# PowerModule_Testboard.net
KiCad netlist of a schematic drawn in EAGLE
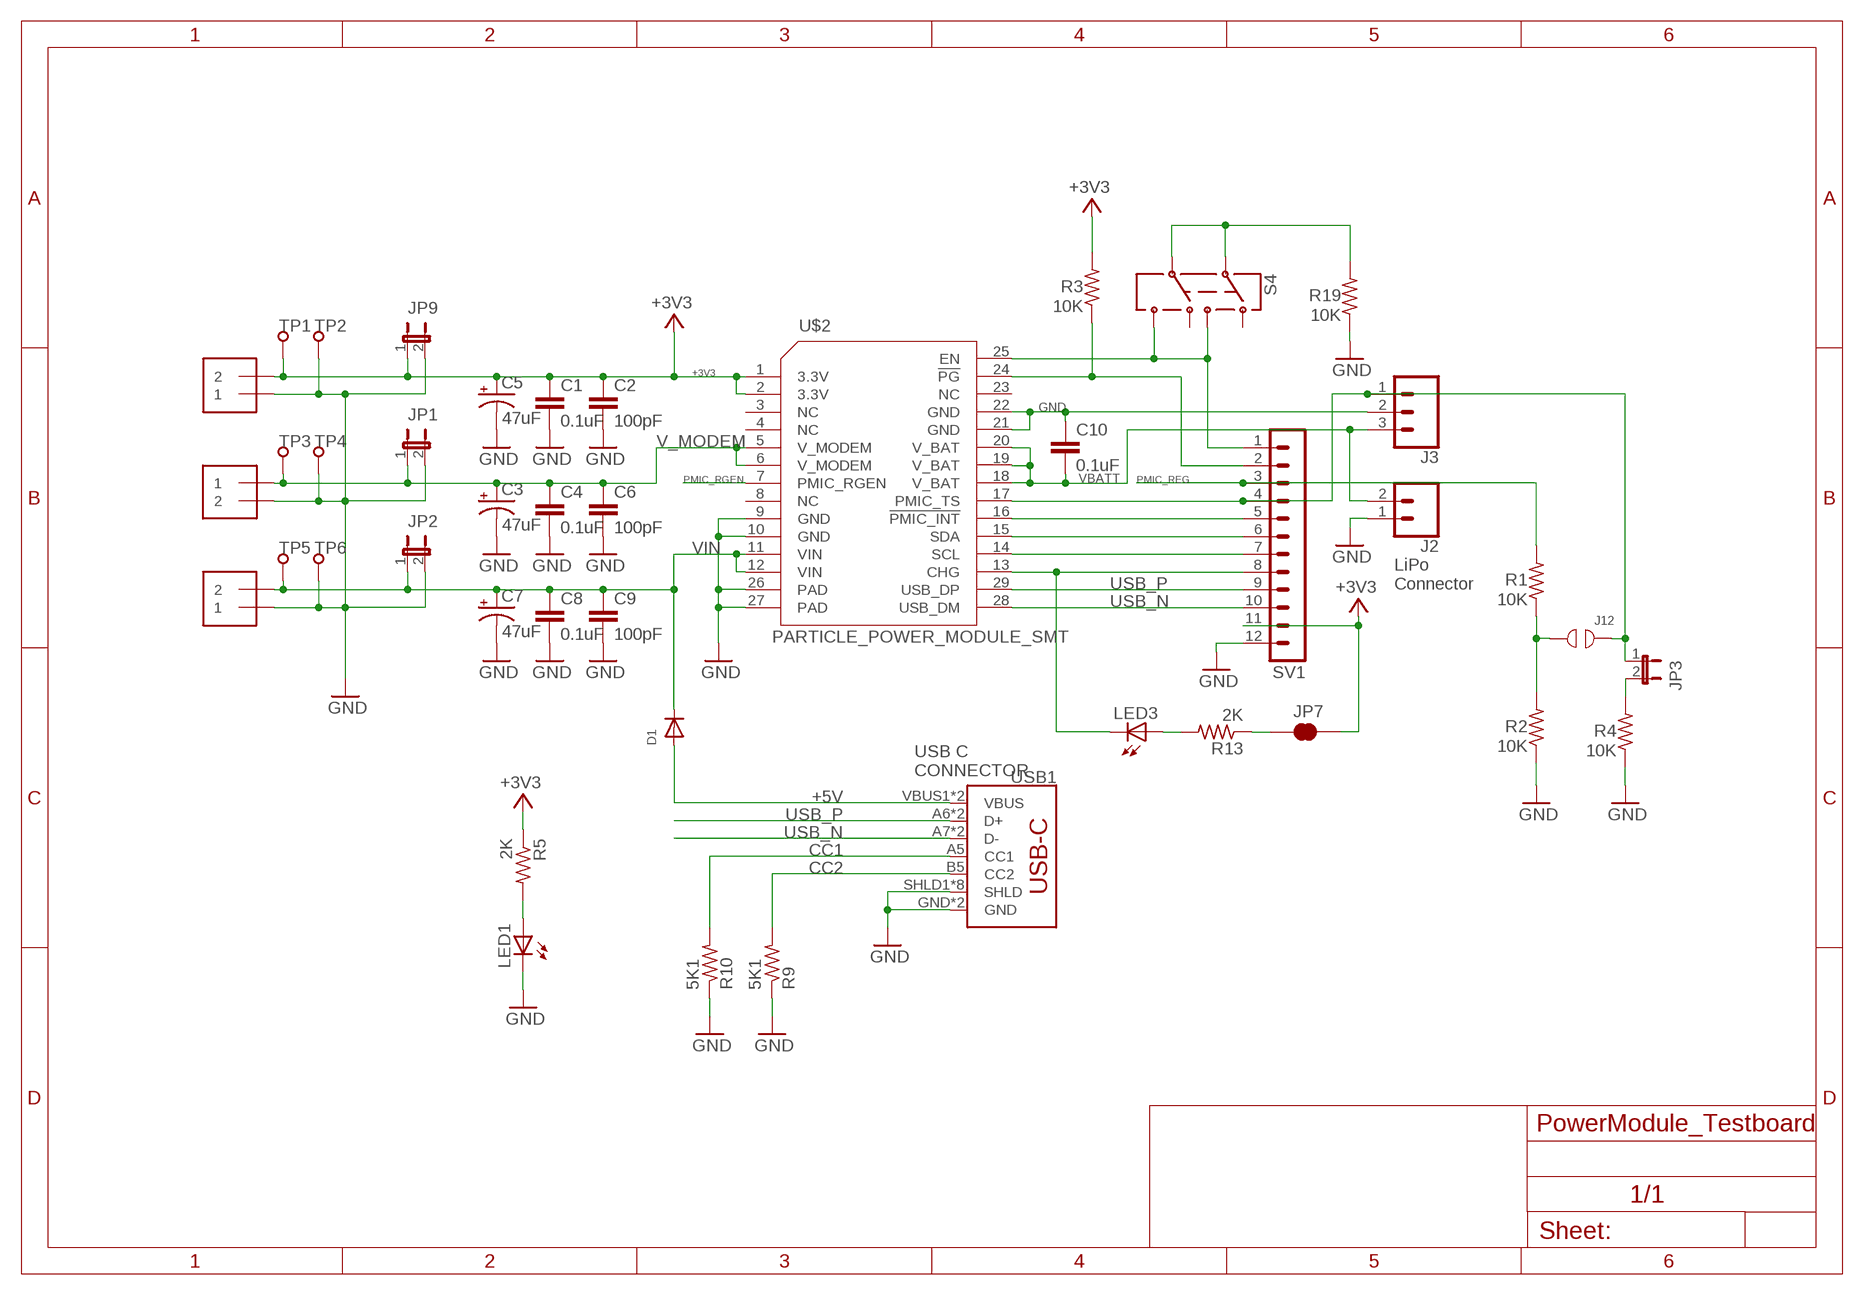
[diagram p0: schematic, sheet 1]

(export (version "E")
  (design (tool "Eeschema 10.0.6"))
  (components
    (comp (ref "C1")
      (value "0.1uF")
      (footprint "eagle-import:0603")
      (libsource (lib "eagle-import") (part "0.1UF-0603-25V-5%"))
    )
    (comp (ref "C2")
      (value "100pF")
      (footprint "eagle-import:0603")
      (libsource (lib "eagle-import") (part "0.1UF-0603-25V-5%"))
    )
    (comp (ref "C3")
      (value "47uF")
      (footprint "eagle-import:NIC_10X10.5_CAP")
      (libsource (lib "eagle-import") (part "100UF-POLAR-10X10.5-63V-20%"))
    )
    (comp (ref "C4")
      (value "0.1uF")
      (footprint "eagle-import:0603")
      (libsource (lib "eagle-import") (part "0.1UF-0603-25V-5%"))
    )
    (comp (ref "C5")
      (value "47uF")
      (footprint "eagle-import:NIC_10X10.5_CAP")
      (libsource (lib "eagle-import") (part "100UF-POLAR-10X10.5-63V-20%"))
    )
    (comp (ref "C6")
      (value "100pF")
      (footprint "eagle-import:0603")
      (libsource (lib "eagle-import") (part "0.1UF-0603-25V-5%"))
    )
    (comp (ref "C7")
      (value "47uF")
      (footprint "eagle-import:NIC_10X10.5_CAP")
      (libsource (lib "eagle-import") (part "100UF-POLAR-10X10.5-63V-20%"))
    )
    (comp (ref "C8")
      (value "0.1uF")
      (footprint "eagle-import:0603")
      (libsource (lib "eagle-import") (part "0.1UF-0603-25V-5%"))
    )
    (comp (ref "C9")
      (value "100pF")
      (footprint "eagle-import:0603")
      (libsource (lib "eagle-import") (part "0.1UF-0603-25V-5%"))
    )
    (comp (ref "C10")
      (value "0.1uF")
      (footprint "eagle-import:0603")
      (libsource (lib "eagle-import") (part "0.1UF-0603-25V-5%"))
    )
    (comp (ref "D1")
      (value "DIODE_SOD-123FL")
      (footprint "eagle-import:SOD-123FL")
      (libsource (lib "eagle-import") (part "DIODE_SOD-123FL"))
    )
    (comp (ref "J1")
      (value "1X2-3.5MM")
      (footprint "eagle-import:1X2-3.5MM")
      (libsource (lib "eagle-import") (part "1X2-3.5MM"))
    )
    (comp (ref "J2")
      (value "CONN_02-JST-2MM-SMT")
      (footprint "eagle-import:JST-2-SMD@2")
      (libsource (lib "eagle-import") (part "CONN_02-JST-2MM-SMT"))
    )
    (comp (ref "J3")
      (value "CONN_03JST-SMD-VERT")
      (footprint "eagle-import:JST-3-SMD-VERT")
      (libsource (lib "eagle-import") (part "CONN_03JST-SMD-VERT"))
    )
    (comp (ref "J4")
      (value "1X2-3.5MM")
      (footprint "eagle-import:1X2-3.5MM")
      (libsource (lib "eagle-import") (part "1X2-3.5MM"))
    )
    (comp (ref "J5")
      (value "1X2-3.5MM")
      (footprint "eagle-import:1X2-3.5MM")
      (libsource (lib "eagle-import") (part "1X2-3.5MM"))
    )
    (comp (ref "J12")
      (value "TP_OPEN")
      (footprint "eagle-import:TP_OPEN")
      (libsource (lib "eagle-import") (part "TP_OPEN"))
    )
    (comp (ref "JP1")
      (value "JUMPER2")
      (footprint "eagle-import:JUMPER2")
      (libsource (lib "eagle-import") (part "JUMPER2"))
    )
    (comp (ref "JP2")
      (value "JUMPER2")
      (footprint "eagle-import:JUMPER2")
      (libsource (lib "eagle-import") (part "JUMPER2"))
    )
    (comp (ref "JP3")
      (value "JUMPER2")
      (footprint "eagle-import:JUMPER2")
      (libsource (lib "eagle-import") (part "JUMPER2"))
    )
    (comp (ref "JP7")
      (value "JUMPER-SMT_2_NC_TRACE_NO-SILK")
      (footprint "eagle-import:SMT-JUMPER_2_NC_TRACE_NO-SILK")
      (libsource (lib "eagle-import") (part "JUMPER-SMT_2_NC_TRACE_NO-SILK"))
    )
    (comp (ref "JP9")
      (value "JUMPER2")
      (footprint "eagle-import:JUMPER2")
      (libsource (lib "eagle-import") (part "JUMPER2"))
    )
    (comp (ref "LED1")
      (value "LEDCHIP-LED0603")
      (footprint "eagle-import:CHIP-LED0603")
      (libsource (lib "eagle-import") (part "LEDCHIP-LED0603"))
    )
    (comp (ref "LED3")
      (value "LEDCHIP-LED0603")
      (footprint "eagle-import:CHIP-LED0603")
      (libsource (lib "eagle-import") (part "LEDCHIP-LED0603"))
    )
    (comp (ref "R1")
      (value "10K")
      (footprint "eagle-import:R0603_P")
      (libsource (lib "eagle-import") (part "RES_0603100K_"))
    )
    (comp (ref "R2")
      (value "10K")
      (footprint "eagle-import:R0603_P")
      (libsource (lib "eagle-import") (part "RES_0603100K_"))
    )
    (comp (ref "R3")
      (value "10K")
      (footprint "eagle-import:R0603_P")
      (libsource (lib "eagle-import") (part "RES_0603100K_"))
    )
    (comp (ref "R4")
      (value "10K")
      (footprint "eagle-import:R0603_P")
      (libsource (lib "eagle-import") (part "RES_0603100K_"))
    )
    (comp (ref "R5")
      (value "2K")
      (footprint "eagle-import:R0603_P")
      (libsource (lib "eagle-import") (part "RES_06032K2_"))
    )
    (comp (ref "R9")
      (value "5K1")
      (footprint "eagle-import:R0603_P")
      (libsource (lib "eagle-import") (part "RES_0603"))
    )
    (comp (ref "R10")
      (value "5K1")
      (footprint "eagle-import:R0603_P")
      (libsource (lib "eagle-import") (part "RES_0603"))
    )
    (comp (ref "R13")
      (value "2K")
      (footprint "eagle-import:R0603_P")
      (libsource (lib "eagle-import") (part "RES_06032K2_"))
    )
    (comp (ref "R19")
      (value "10K")
      (footprint "eagle-import:R0603_P")
      (libsource (lib "eagle-import") (part "RES_0603100K_"))
    )
    (comp (ref "S4")
      (value "SWITCH-DPDT")
      (footprint "eagle-import:SWITCH-2.5X3.2-6")
      (libsource (lib "eagle-import") (part "SWITCH-DPDT"))
    )
    (comp (ref "SV1")
      (value "MA12-1")
      (footprint "eagle-import:MA12-1")
      (libsource (lib "eagle-import") (part "MA12-1"))
    )
    (comp (ref "TP1")
      (value "TP-S2751-46R")
      (footprint "eagle-import:S2751-46R")
      (libsource (lib "eagle-import") (part "TP-S2751-46R"))
    )
    (comp (ref "TP2")
      (value "TP-S2751-46R")
      (footprint "eagle-import:S2751-46R")
      (libsource (lib "eagle-import") (part "TP-S2751-46R"))
    )
    (comp (ref "TP3")
      (value "TP-S2751-46R")
      (footprint "eagle-import:S2751-46R")
      (libsource (lib "eagle-import") (part "TP-S2751-46R"))
    )
    (comp (ref "TP4")
      (value "TP-S2751-46R")
      (footprint "eagle-import:S2751-46R")
      (libsource (lib "eagle-import") (part "TP-S2751-46R"))
    )
    (comp (ref "TP5")
      (value "TP-S2751-46R")
      (footprint "eagle-import:S2751-46R")
      (libsource (lib "eagle-import") (part "TP-S2751-46R"))
    )
    (comp (ref "TP6")
      (value "TP-S2751-46R")
      (footprint "eagle-import:S2751-46R")
      (libsource (lib "eagle-import") (part "TP-S2751-46R"))
    )
    (comp (ref "U$2")
      (value "PARTICLE_POWER_MODULE_SMT")
      (footprint "eagle-import:PARTICLE_POWER_MODULE_SMT")
      (libsource (lib "eagle-import") (part "PARTICLE_POWER_MODULE_SMT"))
    )
    (comp (ref "USB1")
      (value "USB_C16PIN")
      (footprint "eagle-import:USB-C-16P")
      (libsource (lib "eagle-import") (part "USB_C16PIN"))
    )
  )
  (nets
    (net (code "1") (name "+3V3") (class "Default")
      (node (ref "C1") (pin "1") (pinfunction "1_1") (pintype "passive"))
      (node (ref "C2") (pin "1") (pinfunction "1_1") (pintype "passive"))
      (node (ref "C5") (pin "+") (pinfunction "+_+") (pintype "passive"))
      (node (ref "J4") (pin "2") (pinfunction "2_2") (pintype "passive"))
      (node (ref "JP7") (pin "1") (pinfunction "1_1") (pintype "passive"))
      (node (ref "JP9") (pin "1") (pinfunction "1_1") (pintype "passive"))
      (node (ref "R3") (pin "2") (pinfunction "2_2") (pintype "passive"))
      (node (ref "R5") (pin "1") (pinfunction "1_1") (pintype "passive"))
      (node (ref "SV1") (pin "11") (pinfunction "11_11") (pintype "passive"))
      (node (ref "TP1") (pin "1") (pinfunction "TP_1") (pintype "bidirectional"))
      (node (ref "U$2") (pin "1") (pinfunction "3.3V_1") (pintype "bidirectional"))
      (node (ref "U$2") (pin "2") (pinfunction "3.3V_2") (pintype "bidirectional"))
    )
    (net (code "2") (name "/+5V") (class "Default")
      (node (ref "D1") (pin "A") (pinfunction "A_A") (pintype "passive"))
      (node (ref "USB1") (pin "VBUS1") (pinfunction "VBUS_VBUS1") (pintype "bidirectional"))
      (node (ref "USB1") (pin "VBUS2") (pinfunction "VBUS_VBUS2") (pintype "bidirectional"))
    )
    (net (code "3") (name "/CC1") (class "Default")
      (node (ref "R10") (pin "2") (pinfunction "2_2") (pintype "passive"))
      (node (ref "USB1") (pin "A5") (pinfunction "CC1_A5") (pintype "bidirectional"))
    )
    (net (code "4") (name "/CC2") (class "Default")
      (node (ref "R9") (pin "2") (pinfunction "2_2") (pintype "passive"))
      (node (ref "USB1") (pin "B5") (pinfunction "CC2_B5") (pintype "bidirectional"))
    )
    (net (code "5") (name "/PMIC_REG") (class "Default")
      (node (ref "R1") (pin "2") (pinfunction "2_2") (pintype "passive"))
      (node (ref "SV1") (pin "3") (pinfunction "3_3") (pintype "passive"))
    )
    (net (code "6") (name "/PMIC_RGEN") (class "Default")
      (node (ref "U$2") (pin "7") (pinfunction "PMIC_RGEN_7") (pintype "bidirectional"))
    )
    (net (code "7") (name "/USB_N") (class "Default")
      (node (ref "SV1") (pin "10") (pinfunction "10_10") (pintype "passive"))
      (node (ref "U$2") (pin "28") (pinfunction "USB_DM_28") (pintype "bidirectional"))
      (node (ref "USB1") (pin "A7") (pinfunction "D-_A7") (pintype "bidirectional"))
      (node (ref "USB1") (pin "B7") (pinfunction "D-_B7") (pintype "bidirectional"))
    )
    (net (code "8") (name "/USB_P") (class "Default")
      (node (ref "SV1") (pin "9") (pinfunction "9_9") (pintype "passive"))
      (node (ref "U$2") (pin "29") (pinfunction "USB_DP_29") (pintype "bidirectional"))
      (node (ref "USB1") (pin "A6") (pinfunction "D+_A6") (pintype "bidirectional"))
      (node (ref "USB1") (pin "B6") (pinfunction "D+_B6") (pintype "bidirectional"))
    )
    (net (code "9") (name "/VBATT") (class "Default")
      (node (ref "C10") (pin "2") (pinfunction "2_2") (pintype "passive"))
      (node (ref "J2") (pin "2") (pinfunction "1_2") (pintype "passive"))
      (node (ref "J3") (pin "3") (pinfunction "3_3") (pintype "passive"))
      (node (ref "U$2") (pin "18") (pinfunction "V_BAT_18") (pintype "bidirectional"))
      (node (ref "U$2") (pin "19") (pinfunction "V_BAT_19") (pintype "bidirectional"))
      (node (ref "U$2") (pin "20") (pinfunction "V_BAT_20") (pintype "bidirectional"))
    )
    (net (code "10") (name "/VIN") (class "Default")
      (node (ref "C7") (pin "+") (pinfunction "+_+") (pintype "passive"))
      (node (ref "C8") (pin "1") (pinfunction "1_1") (pintype "passive"))
      (node (ref "C9") (pin "1") (pinfunction "1_1") (pintype "passive"))
      (node (ref "D1") (pin "C") (pinfunction "C_C") (pintype "passive"))
      (node (ref "J5") (pin "2") (pinfunction "2_2") (pintype "passive"))
      (node (ref "JP2") (pin "1") (pinfunction "1_1") (pintype "passive"))
      (node (ref "TP5") (pin "1") (pinfunction "TP_1") (pintype "bidirectional"))
      (node (ref "U$2") (pin "11") (pinfunction "VIN_11") (pintype "bidirectional"))
      (node (ref "U$2") (pin "12") (pinfunction "VIN_12") (pintype "bidirectional"))
    )
    (net (code "11") (name "/V_MODEM") (class "Default")
      (node (ref "C3") (pin "+") (pinfunction "+_+") (pintype "passive"))
      (node (ref "C4") (pin "1") (pinfunction "1_1") (pintype "passive"))
      (node (ref "C6") (pin "1") (pinfunction "1_1") (pintype "passive"))
      (node (ref "J1") (pin "1") (pinfunction "1_1") (pintype "passive"))
      (node (ref "JP1") (pin "1") (pinfunction "1_1") (pintype "passive"))
      (node (ref "TP3") (pin "1") (pinfunction "TP_1") (pintype "bidirectional"))
      (node (ref "U$2") (pin "5") (pinfunction "V_MODEM_5") (pintype "bidirectional"))
      (node (ref "U$2") (pin "6") (pinfunction "V_MODEM_6") (pintype "bidirectional"))
    )
    (net (code "12") (name "GND") (class "Default")
      (node (ref "C1") (pin "2") (pinfunction "2_2") (pintype "passive"))
      (node (ref "C10") (pin "1") (pinfunction "1_1") (pintype "passive"))
      (node (ref "C2") (pin "2") (pinfunction "2_2") (pintype "passive"))
      (node (ref "C3") (pin "-") (pinfunction "-_-") (pintype "passive"))
      (node (ref "C4") (pin "2") (pinfunction "2_2") (pintype "passive"))
      (node (ref "C5") (pin "-") (pinfunction "-_-") (pintype "passive"))
      (node (ref "C6") (pin "2") (pinfunction "2_2") (pintype "passive"))
      (node (ref "C7") (pin "-") (pinfunction "-_-") (pintype "passive"))
      (node (ref "C8") (pin "2") (pinfunction "2_2") (pintype "passive"))
      (node (ref "C9") (pin "2") (pinfunction "2_2") (pintype "passive"))
      (node (ref "J1") (pin "2") (pinfunction "2_2") (pintype "passive"))
      (node (ref "J2") (pin "1") (pinfunction "2_1") (pintype "passive"))
      (node (ref "J3") (pin "2") (pinfunction "2_2") (pintype "passive"))
      (node (ref "J4") (pin "1") (pinfunction "1_1") (pintype "passive"))
      (node (ref "J5") (pin "1") (pinfunction "1_1") (pintype "passive"))
      (node (ref "JP1") (pin "2") (pinfunction "2_2") (pintype "passive"))
      (node (ref "JP2") (pin "2") (pinfunction "2_2") (pintype "passive"))
      (node (ref "JP9") (pin "2") (pinfunction "2_2") (pintype "passive"))
      (node (ref "LED1") (pin "C") (pinfunction "C_C") (pintype "passive"))
      (node (ref "R10") (pin "1") (pinfunction "1_1") (pintype "passive"))
      (node (ref "R19") (pin "1") (pinfunction "1_1") (pintype "passive"))
      (node (ref "R2") (pin "1") (pinfunction "1_1") (pintype "passive"))
      (node (ref "R4") (pin "1") (pinfunction "1_1") (pintype "passive"))
      (node (ref "R9") (pin "1") (pinfunction "1_1") (pintype "passive"))
      (node (ref "SV1") (pin "12") (pinfunction "12_12") (pintype "passive"))
      (node (ref "TP2") (pin "1") (pinfunction "TP_1") (pintype "bidirectional"))
      (node (ref "TP4") (pin "1") (pinfunction "TP_1") (pintype "bidirectional"))
      (node (ref "TP6") (pin "1") (pinfunction "TP_1") (pintype "bidirectional"))
      (node (ref "U$2") (pin "10") (pinfunction "GND_10") (pintype "bidirectional"))
      (node (ref "U$2") (pin "21") (pinfunction "GND_21") (pintype "bidirectional"))
      (node (ref "U$2") (pin "22") (pinfunction "GND_22") (pintype "bidirectional"))
      (node (ref "U$2") (pin "26") (pinfunction "PAD_26") (pintype "bidirectional"))
      (node (ref "U$2") (pin "27") (pinfunction "PAD_27") (pintype "bidirectional"))
      (node (ref "U$2") (pin "9") (pinfunction "GND_9") (pintype "bidirectional"))
      (node (ref "USB1") (pin "GND") (pinfunction "GND_GND") (pintype "bidirectional"))
      (node (ref "USB1") (pin "GND2") (pinfunction "GND_GND2") (pintype "bidirectional"))
      (node (ref "USB1") (pin "SHLD1") (pinfunction "SHLD_SHLD1") (pintype "bidirectional"))
      (node (ref "USB1") (pin "SHLD2") (pinfunction "SHLD_SHLD2") (pintype "bidirectional"))
      (node (ref "USB1") (pin "SHLD3") (pinfunction "SHLD_SHLD3") (pintype "bidirectional"))
      (node (ref "USB1") (pin "SHLD4") (pinfunction "SHLD_SHLD4") (pintype "bidirectional"))
      (node (ref "USB1") (pin "SHLD5") (pinfunction "SHLD_SHLD5") (pintype "bidirectional"))
      (node (ref "USB1") (pin "SHLD6") (pinfunction "SHLD_SHLD6") (pintype "bidirectional"))
      (node (ref "USB1") (pin "SHLD7") (pinfunction "SHLD_SHLD7") (pintype "bidirectional"))
      (node (ref "USB1") (pin "SHLD8") (pinfunction "SHLD_SHLD8") (pintype "bidirectional"))
    )
    (net (code "13") (name "Net-(J12-Pad1)") (class "Default")
      (node (ref "J12") (pin "1") (pinfunction "1_1") (pintype "bidirectional"))
      (node (ref "R1") (pin "1") (pinfunction "1_1") (pintype "passive"))
      (node (ref "R2") (pin "2") (pinfunction "2_2") (pintype "passive"))
    )
    (net (code "14") (name "Net-(JP3-Pad2)") (class "Default")
      (node (ref "JP3") (pin "2") (pinfunction "2_2") (pintype "passive"))
      (node (ref "R4") (pin "2") (pinfunction "2_2") (pintype "passive"))
    )
    (net (code "15") (name "Net-(JP7-Pad2)") (class "Default")
      (node (ref "JP7") (pin "2") (pinfunction "2_2") (pintype "passive"))
      (node (ref "R13") (pin "1") (pinfunction "1_1") (pintype "passive"))
    )
    (net (code "16") (name "Net-(LED1-PadA)") (class "Default")
      (node (ref "LED1") (pin "A") (pinfunction "A_A") (pintype "passive"))
      (node (ref "R5") (pin "2") (pinfunction "2_2") (pintype "passive"))
    )
    (net (code "17") (name "Net-(LED3-PadA)") (class "Default")
      (node (ref "LED3") (pin "A") (pinfunction "A_A") (pintype "passive"))
      (node (ref "R13") (pin "2") (pinfunction "2_2") (pintype "passive"))
    )
    (net (code "18") (name "Net-(R19-Pad2)") (class "Default")
      (node (ref "R19") (pin "2") (pinfunction "2_2") (pintype "passive"))
      (node (ref "S4") (pin "2") (pinfunction "2_2") (pintype "bidirectional"))
      (node (ref "S4") (pin "5") (pinfunction "5_5") (pintype "bidirectional"))
    )
    (net (code "19") (name "Net-(U$2-CHG)") (class "Default")
      (node (ref "LED3") (pin "C") (pinfunction "C_C") (pintype "passive"))
      (node (ref "SV1") (pin "8") (pinfunction "8_8") (pintype "passive"))
      (node (ref "U$2") (pin "13") (pinfunction "CHG_13") (pintype "bidirectional"))
    )
    (net (code "20") (name "Net-(U$2-EN)") (class "Default")
      (node (ref "S4") (pin "3") (pinfunction "3_3") (pintype "bidirectional"))
      (node (ref "S4") (pin "6") (pinfunction "6_6") (pintype "bidirectional"))
      (node (ref "SV1") (pin "1") (pinfunction "1_1") (pintype "passive"))
      (node (ref "U$2") (pin "25") (pinfunction "EN_25") (pintype "bidirectional"))
    )
    (net (code "21") (name "Net-(U$2-PMIC_TS)") (class "Default")
      (node (ref "J12") (pin "2") (pinfunction "2_2") (pintype "bidirectional"))
      (node (ref "J3") (pin "1") (pinfunction "1_1") (pintype "passive"))
      (node (ref "JP3") (pin "1") (pinfunction "1_1") (pintype "passive"))
      (node (ref "SV1") (pin "4") (pinfunction "4_4") (pintype "passive"))
      (node (ref "U$2") (pin "17") (pinfunction "PMIC_TS_17") (pintype "bidirectional"))
    )
    (net (code "22") (name "Net-(U$2-SCL)") (class "Default")
      (node (ref "SV1") (pin "7") (pinfunction "7_7") (pintype "passive"))
      (node (ref "U$2") (pin "14") (pinfunction "SCL_14") (pintype "bidirectional"))
    )
    (net (code "23") (name "Net-(U$2-SDA)") (class "Default")
      (node (ref "SV1") (pin "6") (pinfunction "6_6") (pintype "passive"))
      (node (ref "U$2") (pin "15") (pinfunction "SDA_15") (pintype "bidirectional"))
    )
    (net (code "24") (name "Net-(U$2-~{PG})") (class "Default")
      (node (ref "R3") (pin "1") (pinfunction "1_1") (pintype "passive"))
      (node (ref "SV1") (pin "2") (pinfunction "2_2") (pintype "passive"))
      (node (ref "U$2") (pin "24") (pinfunction "~{PG}_24") (pintype "bidirectional"))
    )
    (net (code "25") (name "Net-(U$2-~{PMIC_INT})") (class "Default")
      (node (ref "SV1") (pin "5") (pinfunction "5_5") (pintype "passive"))
      (node (ref "U$2") (pin "16") (pinfunction "~{PMIC_INT}_16") (pintype "bidirectional"))
    )
    (net (code "26") (name "unconnected-(S4-Pad1)") (class "Default")
      (node (ref "S4") (pin "1") (pinfunction "1_1") (pintype "bidirectional"))
    )
    (net (code "27") (name "unconnected-(S4-Pad4)") (class "Default")
      (node (ref "S4") (pin "4") (pinfunction "4_4") (pintype "bidirectional"))
    )
    (net (code "28") (name "unconnected-(U$2-NC-Pad3)") (class "Default")
      (node (ref "U$2") (pin "3") (pinfunction "NC_3") (pintype "bidirectional"))
    )
    (net (code "29") (name "unconnected-(U$2-NC-Pad4)") (class "Default")
      (node (ref "U$2") (pin "4") (pinfunction "NC_4") (pintype "bidirectional"))
    )
    (net (code "30") (name "unconnected-(U$2-NC-Pad8)") (class "Default")
      (node (ref "U$2") (pin "8") (pinfunction "NC_8") (pintype "bidirectional"))
    )
    (net (code "31") (name "unconnected-(U$2-NC-Pad23)") (class "Default")
      (node (ref "U$2") (pin "23") (pinfunction "NC_23") (pintype "bidirectional"))
    )
  )
)
